# AGV_Schematic.net
KiCad netlist of a schematic drawn in Altium Designer
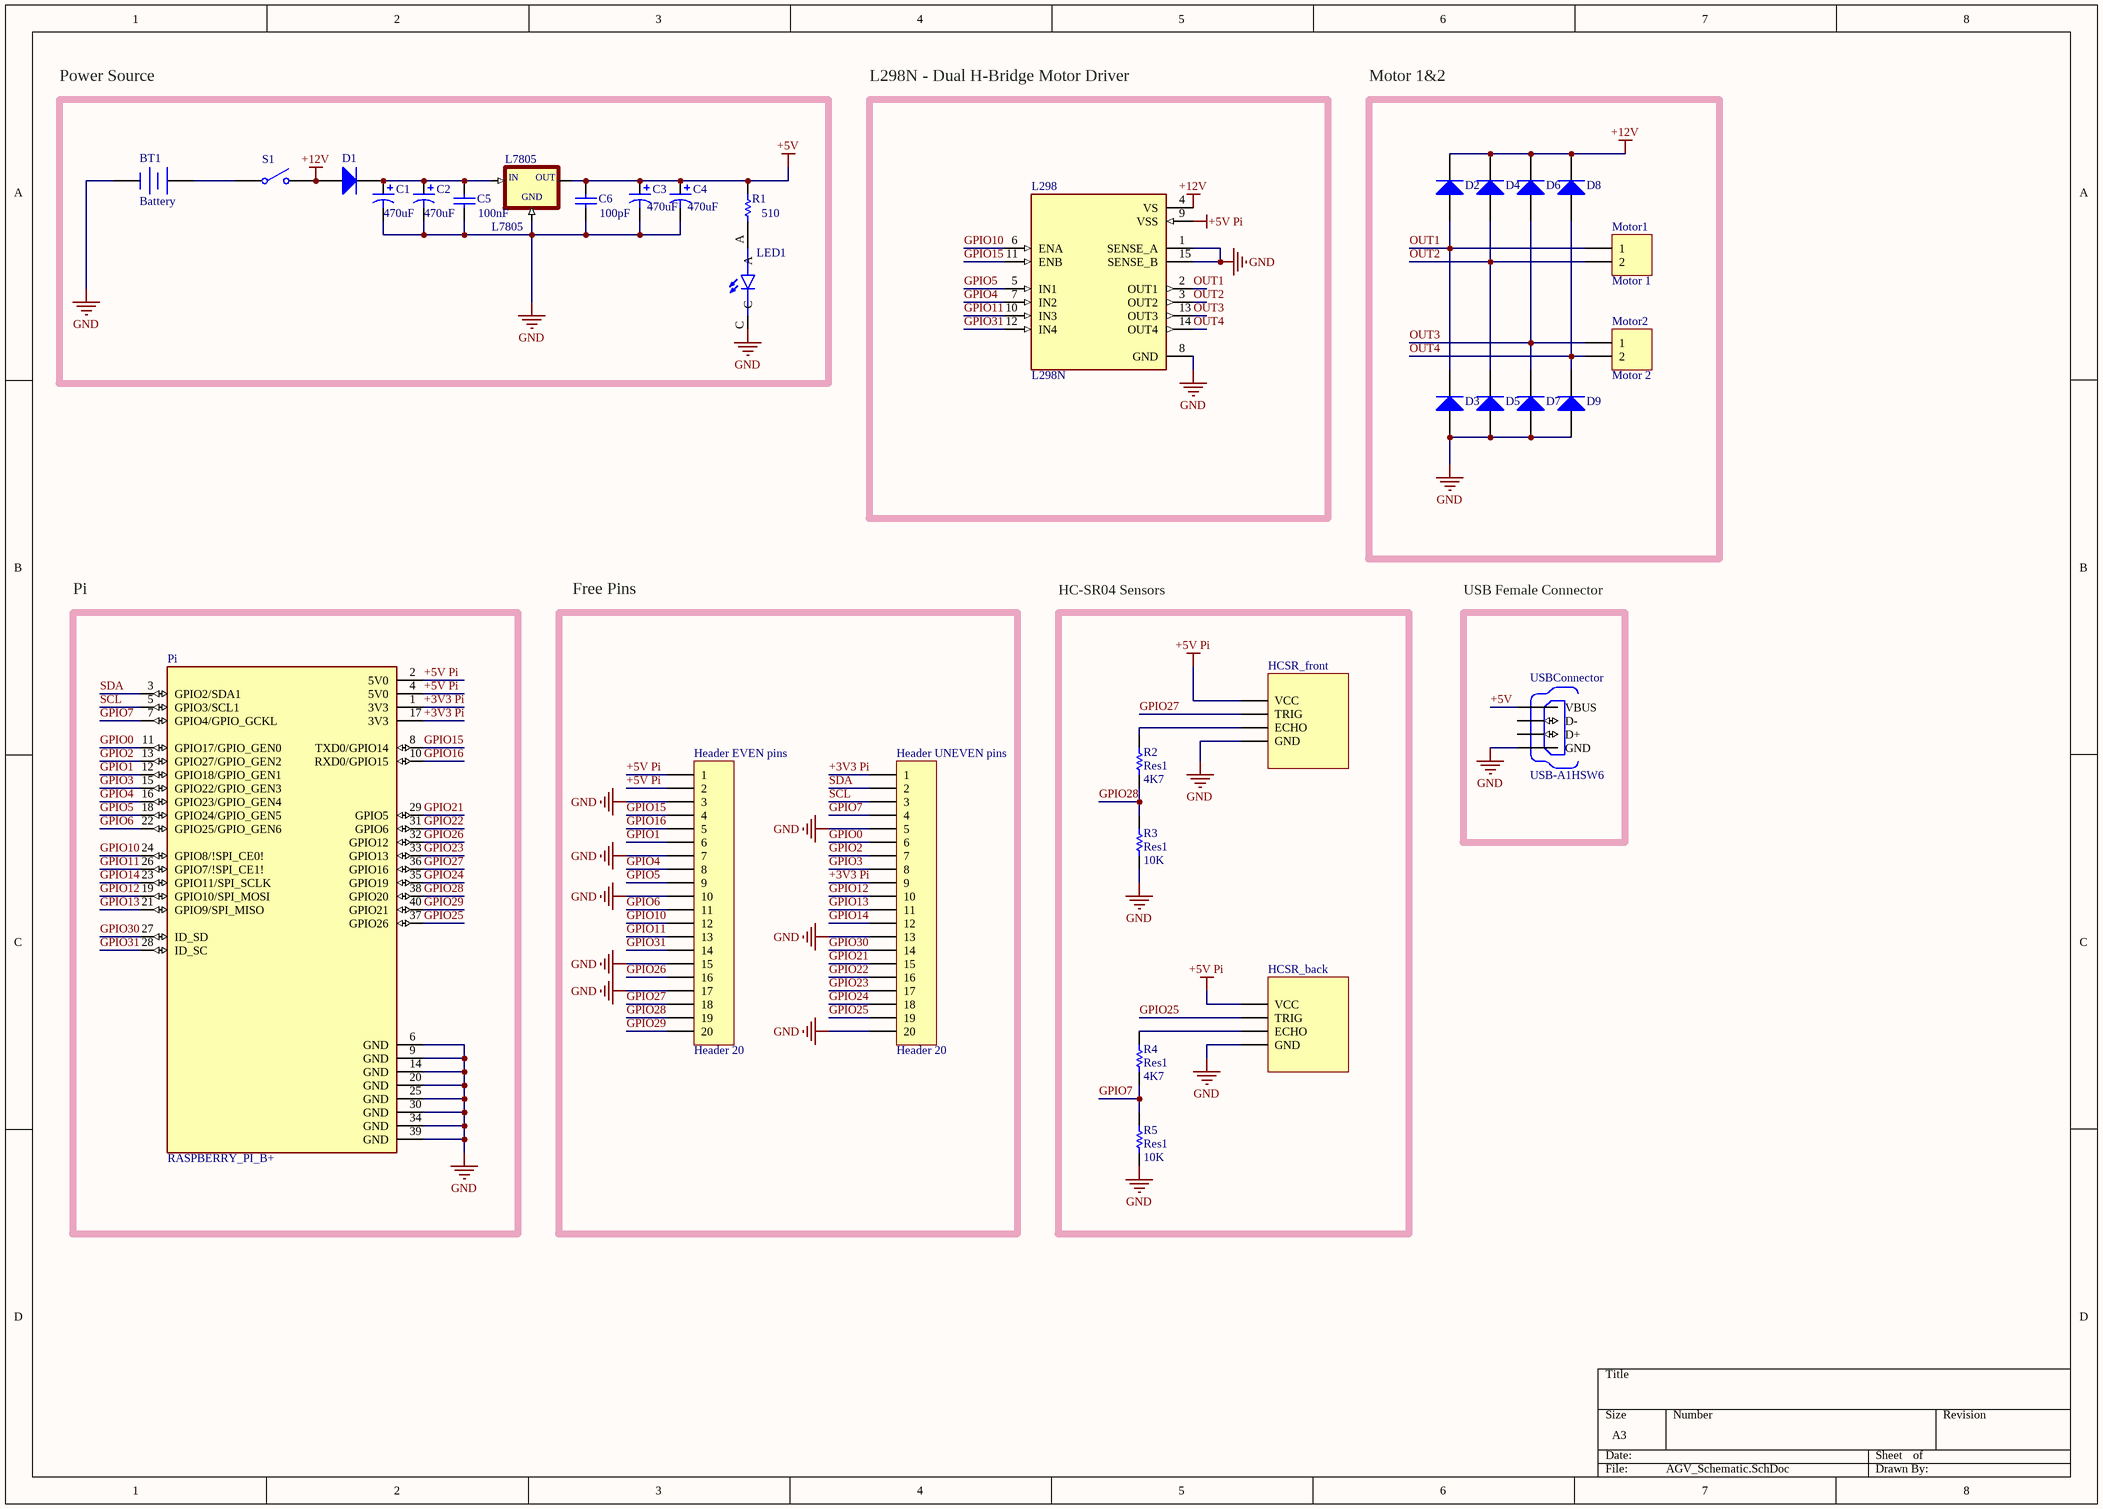
[diagram p0: AGV_Schematic.SchDoc]

(export (version "E")
  (design (tool "Eeschema 10.0.6"))
  (components
    (comp (ref "BT1")
      (value "Battery")
      (footprint "PCBComponent_1")
      (description "Multicell Battery")
      (fields (field (name "PUBLISHER") "Altium Limited"))
      (libsource (lib "Miscellaneous Devices") (part "Battery"))
    )
    (comp (ref "C1")
      (value "470uF")
      (footprint "elektrolitski_kond:Elektrolitski kondenzator")
      (description "Polarized Capacitor (Radial)")
      (fields (field (name "Comment") "Cap Pol1") (field (name "PUBLISHER") "Altium Limited"))
      (libsource (lib "elektrolitski_kond") (part "Elektrolitski kondenzator"))
    )
    (comp (ref "C2")
      (value "470uF")
      (footprint "elektrolitski_kond:Elektrolitski kondenzator")
      (description "Polarized Capacitor (Radial)")
      (fields (field (name "Comment") "Cap Pol1") (field (name "PUBLISHER") "Altium Limited"))
      (libsource (lib "elektrolitski_kond") (part "Elektrolitski kondenzator"))
    )
    (comp (ref "C3")
      (value "470uF")
      (footprint "elektrolitski_kond:Elektrolitski kondenzator")
      (description "Polarized Capacitor (Radial)")
      (fields (field (name "Comment") "Cap Pol1") (field (name "PUBLISHER") "Altium Limited"))
      (libsource (lib "elektrolitski_kond") (part "Elektrolitski kondenzator"))
    )
    (comp (ref "C4")
      (value "470uF")
      (footprint "elektrolitski_kond:Elektrolitski kondenzator")
      (description "Polarized Capacitor (Radial)")
      (fields (field (name "Comment") "Cap Pol1") (field (name "PUBLISHER") "Altium Limited"))
      (libsource (lib "elektrolitski_kond") (part "Elektrolitski kondenzator"))
    )
    (comp (ref "C5")
      (value "100nF")
      (footprint "CAP:CAP140")
      (description "Capacitor")
      (fields (field (name "Comment") "Cap") (field (name "PUBLISHER") "Altium Limited"))
      (libsource (lib "Miscellaneous Devices") (part "Cap"))
    )
    (comp (ref "C6")
      (value "100pF")
      (footprint "CAP:CAP140")
      (description "Capacitor")
      (fields (field (name "Comment") "Cap") (field (name "PUBLISHER") "Altium Limited"))
      (libsource (lib "Miscellaneous Devices") (part "Cap"))
    )
    (comp (ref "D1")
      (value "Diode 1N4007")
      (footprint "DO-41")
      (description "1 Amp General Purpose Rectifier")
      (fields (field (name "PUBLISHER") "Altium Limited"))
      (libsource (lib "Miscellaneous Devices") (part "Diode 1N4007"))
    )
    (comp (ref "D2")
      (value "Diode 1N5402")
      (footprint "DO-41")
      (description "3 Amp General Purpose Rectifier")
      (fields (field (name "PUBLISHER") "Altium Limited"))
      (libsource (lib "Miscellaneous Devices") (part "Diode 1N5402"))
    )
    (comp (ref "D3")
      (value "Diode 1N5402")
      (footprint "DO-41")
      (description "3 Amp General Purpose Rectifier")
      (fields (field (name "PUBLISHER") "Altium Limited"))
      (libsource (lib "Miscellaneous Devices") (part "Diode 1N5402"))
    )
    (comp (ref "D4")
      (value "Diode 1N5402")
      (footprint "DO-41")
      (description "3 Amp General Purpose Rectifier")
      (fields (field (name "PUBLISHER") "Altium Limited"))
      (libsource (lib "Miscellaneous Devices") (part "Diode 1N5402"))
    )
    (comp (ref "D5")
      (value "Diode 1N5402")
      (footprint "DO-41")
      (description "3 Amp General Purpose Rectifier")
      (fields (field (name "PUBLISHER") "Altium Limited"))
      (libsource (lib "Miscellaneous Devices") (part "Diode 1N5402"))
    )
    (comp (ref "D6")
      (value "Diode 1N5402")
      (footprint "DO-41")
      (description "3 Amp General Purpose Rectifier")
      (fields (field (name "PUBLISHER") "Altium Limited"))
      (libsource (lib "Miscellaneous Devices") (part "Diode 1N5402"))
    )
    (comp (ref "D7")
      (value "Diode 1N5402")
      (footprint "DO-41")
      (description "3 Amp General Purpose Rectifier")
      (fields (field (name "PUBLISHER") "Altium Limited"))
      (libsource (lib "Miscellaneous Devices") (part "Diode 1N5402"))
    )
    (comp (ref "D8")
      (value "Diode 1N5402")
      (footprint "DO-41")
      (description "3 Amp General Purpose Rectifier")
      (fields (field (name "PUBLISHER") "Altium Limited"))
      (libsource (lib "Miscellaneous Devices") (part "Diode 1N5402"))
    )
    (comp (ref "D9")
      (value "Diode 1N5402")
      (footprint "DO-41")
      (description "3 Amp General Purpose Rectifier")
      (fields (field (name "PUBLISHER") "Altium Limited"))
      (libsource (lib "Miscellaneous Devices") (part "Diode 1N5402"))
    )
    (comp (ref "HCSR_back") (value "~") (footprint "HDR1X4") (libsource (lib "Komponente") (part "HC-SR04")))
    (comp (ref "HCSR_front") (value "~") (footprint "HDR1X4") (libsource (lib "Komponente") (part "HC-SR04")))
    (comp (ref "Header EVEN pins")
      (value "Header 20")
      (footprint "HDR1X20")
      (description "Header, 20-Pin")
      (fields (field (name "PUBLISHER") "Altium Limited"))
      (libsource (lib "Miscellaneous Connectors") (part "Header 20"))
    )
    (comp (ref "Header UNEVEN pins")
      (value "Header 20")
      (footprint "HDR1X20")
      (description "Header, 20-Pin")
      (fields (field (name "PUBLISHER") "Altium Limited"))
      (libsource (lib "Miscellaneous Connectors") (part "Header 20"))
    )
    (comp (ref "L298")
      (value "L298N")
      (footprint "TO127P2020X500X2100-15")
      (description "Dual Full Bridge Motor Driver 15-Pin(15+Tab) MULTIWATT V Tube")
      (libsource (lib "L298N") (part "L298N"))
    )
    (comp (ref "L7805")
      (value "L7805")
      (footprint "78XXS")
      (description "Linear Voltage Regulator IC 1 Output 1.5A D2PAK")
      (fields (field (name "MF") "STMicroelectronics"))
      (libsource (lib "L7805") (part "L7805"))
    )
    (comp (ref "LED1")
      (value "*")
      (footprint "LED_WP7113LGD")
      (fields (field (name "MP") "WP7113LGD") (field (name "MF") "Kingbright"))
      (libsource (lib "WP7113LGD") (part "WP7113LGD"))
    )
    (comp (ref "Motor1")
      (value "Motor 1")
      (footprint "PCBComponent_1")
      (description "Header, 2-Pin")
      (fields (field (name "PUBLISHER") "Altium Limited"))
      (libsource (lib "Miscellaneous Connectors") (part "Header 2"))
    )
    (comp (ref "Motor2")
      (value "Motor 2")
      (footprint "PCBComponent_1")
      (description "Header, 2-Pin")
      (fields (field (name "PUBLISHER") "Altium Limited"))
      (libsource (lib "Miscellaneous Connectors") (part "Header 2"))
    )
    (comp (ref "Pi")
      (value "RASPBERRY_PI_B+")
      (footprint "PiMirror")
      (description "BCM2835 Raspberry Pi Model B+ - ARM11, VideoCore MPU Embedded Evaluation Board")
      (fields (field (name "MF") "Raspberry Pi") (field (name "MP") "RASPBERRY PI B+"))
      (libsource (lib "RASPBERRY_PI_B_") (part "RASPBERRY_PI_B+"))
    )
    (comp (ref "R1")
      (value "510")
      (footprint "AXIAL-0.3")
      (description "Resistor")
      (fields (field (name "Comment") "Res1") (field (name "PUBLISHER") "Altium Limited"))
      (libsource (lib "Miscellaneous Devices") (part "Res1"))
    )
    (comp (ref "R2")
      (value "Res1")
      (footprint "AXIAL-0.3")
      (description "Resistor")
      (fields (field (name "ALTIUM_VALUE") "4K7") (field (name "PUBLISHER") "Altium Limited"))
      (libsource (lib "Miscellaneous Devices") (part "Res1"))
    )
    (comp (ref "R3")
      (value "Res1")
      (footprint "AXIAL-0.3")
      (description "Resistor")
      (fields (field (name "ALTIUM_VALUE") "10K") (field (name "PUBLISHER") "Altium Limited"))
      (libsource (lib "Miscellaneous Devices") (part "Res1"))
    )
    (comp (ref "R4")
      (value "Res1")
      (footprint "AXIAL-0.3")
      (description "Resistor")
      (fields (field (name "ALTIUM_VALUE") "4K7") (field (name "PUBLISHER") "Altium Limited"))
      (libsource (lib "Miscellaneous Devices") (part "Res1"))
    )
    (comp (ref "R5")
      (value "Res1")
      (footprint "AXIAL-0.3")
      (description "Resistor")
      (fields (field (name "ALTIUM_VALUE") "10K") (field (name "PUBLISHER") "Altium Limited"))
      (libsource (lib "Miscellaneous Devices") (part "Res1"))
    )
    (comp (ref "S1")
      (value "SW-SPST")
      (footprint "Prekidac:Prekidac")
      (description "Single-Pole, Single-Throw Switch")
      (fields (field (name "PUBLISHER") "Altium Limited"))
      (libsource (lib "Miscellaneous Devices") (part "SW-SPST"))
    )
    (comp (ref "USBConnector")
      (value "USB-A1HSW6")
      (footprint "OST_USB-A1HSW6")
      (description "USB-A (USB TYPE-A) - Receptacle Connector 4 Position Through Hole, Right Angle")
      (fields (field (name "MF") "On Shore"))
      (libsource (lib "USB-A1HSW6") (part "USB-A1HSW6"))
    )
  )
  (nets
    (net (code "1") (name "+5V") (class "Default")
      (node (ref "C3") (pin "1") (pinfunction "1_1") (pintype "passive"))
      (node (ref "C4") (pin "1") (pinfunction "1_1") (pintype "passive"))
      (node (ref "C6") (pin "2") (pinfunction "2_2") (pintype "passive"))
      (node (ref "L7805") (pin "OUT") (pinfunction "OUT_OUT") (pintype "passive"))
      (node (ref "R1") (pin "2") (pinfunction "2_2") (pintype "passive"))
      (node (ref "USBConnector") (pin "1") (pinfunction "VBUS_1") (pintype "power_in"))
    )
    (net (code "2") (name "+5V Pi") (class "Default")
      (node (ref "HCSR_back") (pin "1") (pinfunction "VCC_1") (pintype "passive"))
      (node (ref "HCSR_front") (pin "1") (pinfunction "VCC_1") (pintype "passive"))
      (node (ref "Header EVEN pins") (pin "1") (pinfunction "1_1") (pintype "passive"))
      (node (ref "Header EVEN pins") (pin "2") (pinfunction "2_2") (pintype "passive"))
      (node (ref "L298") (pin "9") (pinfunction "VSS_9") (pintype "input"))
      (node (ref "Pi") (pin "2") (pinfunction "5V0_2") (pintype "power_in"))
      (node (ref "Pi") (pin "4") (pinfunction "5V0_4") (pintype "power_in"))
    )
    (net (code "3") (name "+12V") (class "Default")
      (node (ref "D1") (pin "1") (pinfunction "A_1") (pintype "passive"))
      (node (ref "D2") (pin "2") (pinfunction "K_2") (pintype "passive"))
      (node (ref "D4") (pin "2") (pinfunction "K_2") (pintype "passive"))
      (node (ref "D6") (pin "2") (pinfunction "K_2") (pintype "passive"))
      (node (ref "D8") (pin "2") (pinfunction "K_2") (pintype "passive"))
      (node (ref "L298") (pin "4") (pinfunction "VS_4") (pintype "power_in"))
      (node (ref "S1") (pin "2") (pinfunction "NO_2") (pintype "passive"))
    )
    (net (code "4") (name "/+3V3 Pi") (class "Default")
      (node (ref "Header UNEVEN pins") (pin "1") (pinfunction "1_1") (pintype "passive"))
      (node (ref "Header UNEVEN pins") (pin "9") (pinfunction "9_9") (pintype "passive"))
      (node (ref "Pi") (pin "1") (pinfunction "3V3_1") (pintype "power_in"))
      (node (ref "Pi") (pin "17") (pinfunction "3V3_17") (pintype "power_in"))
    )
    (net (code "5") (name "/GPIO0") (class "Default")
      (node (ref "Header UNEVEN pins") (pin "6") (pinfunction "6_6") (pintype "passive"))
      (node (ref "Pi") (pin "11") (pinfunction "GPIO17/GPIO_GEN0_11") (pintype "bidirectional"))
    )
    (net (code "6") (name "/GPIO1") (class "Default")
      (node (ref "Header EVEN pins") (pin "6") (pinfunction "6_6") (pintype "passive"))
      (node (ref "Pi") (pin "12") (pinfunction "GPIO18/GPIO_GEN1_12") (pintype "bidirectional"))
    )
    (net (code "7") (name "/GPIO2") (class "Default")
      (node (ref "Header UNEVEN pins") (pin "7") (pinfunction "7_7") (pintype "passive"))
      (node (ref "Pi") (pin "13") (pinfunction "GPIO27/GPIO_GEN2_13") (pintype "bidirectional"))
    )
    (net (code "8") (name "/GPIO3") (class "Default")
      (node (ref "Header UNEVEN pins") (pin "8") (pinfunction "8_8") (pintype "passive"))
      (node (ref "Pi") (pin "15") (pinfunction "GPIO22/GPIO_GEN3_15") (pintype "bidirectional"))
    )
    (net (code "9") (name "/GPIO4") (class "Default")
      (node (ref "Header EVEN pins") (pin "8") (pinfunction "8_8") (pintype "passive"))
      (node (ref "L298") (pin "7") (pinfunction "IN2_7") (pintype "input"))
      (node (ref "Pi") (pin "16") (pinfunction "GPIO23/GPIO_GEN4_16") (pintype "bidirectional"))
    )
    (net (code "10") (name "/GPIO5") (class "Default")
      (node (ref "Header EVEN pins") (pin "9") (pinfunction "9_9") (pintype "passive"))
      (node (ref "L298") (pin "5") (pinfunction "IN1_5") (pintype "input"))
      (node (ref "Pi") (pin "18") (pinfunction "GPIO24/GPIO_GEN5_18") (pintype "bidirectional"))
    )
    (net (code "11") (name "/GPIO6") (class "Default")
      (node (ref "Header EVEN pins") (pin "11") (pinfunction "11_11") (pintype "passive"))
      (node (ref "Pi") (pin "22") (pinfunction "GPIO25/GPIO_GEN6_22") (pintype "bidirectional"))
    )
    (net (code "12") (name "/GPIO7") (class "Default")
      (node (ref "Header UNEVEN pins") (pin "4") (pinfunction "4_4") (pintype "passive"))
      (node (ref "Pi") (pin "7") (pinfunction "GPIO4/GPIO_GCKL_7") (pintype "bidirectional"))
      (node (ref "R4") (pin "1") (pinfunction "1_1") (pintype "passive"))
      (node (ref "R5") (pin "2") (pinfunction "2_2") (pintype "passive"))
    )
    (net (code "13") (name "/GPIO10") (class "Default")
      (node (ref "Header EVEN pins") (pin "12") (pinfunction "12_12") (pintype "passive"))
      (node (ref "L298") (pin "6") (pinfunction "ENA_6") (pintype "input"))
      (node (ref "Pi") (pin "24") (pinfunction "GPIO8/!SPI_CE0!_24") (pintype "bidirectional"))
    )
    (net (code "14") (name "/GPIO11") (class "Default")
      (node (ref "Header EVEN pins") (pin "13") (pinfunction "13_13") (pintype "passive"))
      (node (ref "L298") (pin "10") (pinfunction "IN3_10") (pintype "input"))
      (node (ref "Pi") (pin "26") (pinfunction "GPIO7/!SPI_CE1!_26") (pintype "bidirectional"))
    )
    (net (code "15") (name "/GPIO12") (class "Default")
      (node (ref "Header UNEVEN pins") (pin "10") (pinfunction "10_10") (pintype "passive"))
      (node (ref "Pi") (pin "19") (pinfunction "GPIO10/SPI_MOSI_19") (pintype "bidirectional"))
    )
    (net (code "16") (name "/GPIO13") (class "Default")
      (node (ref "Header UNEVEN pins") (pin "11") (pinfunction "11_11") (pintype "passive"))
      (node (ref "Pi") (pin "21") (pinfunction "GPIO9/SPI_MISO_21") (pintype "bidirectional"))
    )
    (net (code "17") (name "/GPIO14") (class "Default")
      (node (ref "Header UNEVEN pins") (pin "12") (pinfunction "12_12") (pintype "passive"))
      (node (ref "Pi") (pin "23") (pinfunction "GPIO11/SPI_SCLK_23") (pintype "bidirectional"))
    )
    (net (code "18") (name "/GPIO15") (class "Default")
      (node (ref "Header EVEN pins") (pin "4") (pinfunction "4_4") (pintype "passive"))
      (node (ref "L298") (pin "11") (pinfunction "ENB_11") (pintype "input"))
      (node (ref "Pi") (pin "8") (pinfunction "TXD0/GPIO14_8") (pintype "bidirectional"))
    )
    (net (code "19") (name "/GPIO16") (class "Default")
      (node (ref "Header EVEN pins") (pin "5") (pinfunction "5_5") (pintype "passive"))
      (node (ref "Pi") (pin "10") (pinfunction "RXD0/GPIO15_10") (pintype "bidirectional"))
    )
    (net (code "20") (name "/GPIO21") (class "Default")
      (node (ref "Header UNEVEN pins") (pin "15") (pinfunction "15_15") (pintype "passive"))
      (node (ref "Pi") (pin "29") (pinfunction "GPIO5_29") (pintype "bidirectional"))
    )
    (net (code "21") (name "/GPIO22") (class "Default")
      (node (ref "Header UNEVEN pins") (pin "16") (pinfunction "16_16") (pintype "passive"))
      (node (ref "Pi") (pin "31") (pinfunction "GPIO6_31") (pintype "bidirectional"))
    )
    (net (code "22") (name "/GPIO23") (class "Default")
      (node (ref "Header UNEVEN pins") (pin "17") (pinfunction "17_17") (pintype "passive"))
      (node (ref "Pi") (pin "33") (pinfunction "GPIO13_33") (pintype "bidirectional"))
    )
    (net (code "23") (name "/GPIO24") (class "Default")
      (node (ref "Header UNEVEN pins") (pin "18") (pinfunction "18_18") (pintype "passive"))
      (node (ref "Pi") (pin "35") (pinfunction "GPIO19_35") (pintype "bidirectional"))
    )
    (net (code "24") (name "/GPIO25") (class "Default")
      (node (ref "HCSR_back") (pin "2") (pinfunction "TRIG_2") (pintype "passive"))
      (node (ref "Header UNEVEN pins") (pin "19") (pinfunction "19_19") (pintype "passive"))
      (node (ref "Pi") (pin "37") (pinfunction "GPIO26_37") (pintype "bidirectional"))
    )
    (net (code "25") (name "/GPIO26") (class "Default")
      (node (ref "Header EVEN pins") (pin "16") (pinfunction "16_16") (pintype "passive"))
      (node (ref "Pi") (pin "32") (pinfunction "GPIO12_32") (pintype "bidirectional"))
    )
    (net (code "26") (name "/GPIO27") (class "Default")
      (node (ref "HCSR_front") (pin "2") (pinfunction "TRIG_2") (pintype "passive"))
      (node (ref "Header EVEN pins") (pin "18") (pinfunction "18_18") (pintype "passive"))
      (node (ref "Pi") (pin "36") (pinfunction "GPIO16_36") (pintype "bidirectional"))
    )
    (net (code "27") (name "/GPIO28") (class "Default")
      (node (ref "Header EVEN pins") (pin "19") (pinfunction "19_19") (pintype "passive"))
      (node (ref "Pi") (pin "38") (pinfunction "GPIO20_38") (pintype "bidirectional"))
      (node (ref "R2") (pin "1") (pinfunction "1_1") (pintype "passive"))
      (node (ref "R3") (pin "2") (pinfunction "2_2") (pintype "passive"))
    )
    (net (code "28") (name "/GPIO29") (class "Default")
      (node (ref "Header EVEN pins") (pin "20") (pinfunction "20_20") (pintype "passive"))
      (node (ref "Pi") (pin "40") (pinfunction "GPIO21_40") (pintype "bidirectional"))
    )
    (net (code "29") (name "/GPIO30") (class "Default")
      (node (ref "Header UNEVEN pins") (pin "14") (pinfunction "14_14") (pintype "passive"))
      (node (ref "Pi") (pin "27") (pinfunction "ID_SD_27") (pintype "bidirectional"))
    )
    (net (code "30") (name "/GPIO31") (class "Default")
      (node (ref "Header EVEN pins") (pin "14") (pinfunction "14_14") (pintype "passive"))
      (node (ref "L298") (pin "12") (pinfunction "IN4_12") (pintype "input"))
      (node (ref "Pi") (pin "28") (pinfunction "ID_SC_28") (pintype "bidirectional"))
    )
    (net (code "31") (name "/OUT1") (class "Default")
      (node (ref "D2") (pin "1") (pinfunction "A_1") (pintype "passive"))
      (node (ref "D3") (pin "2") (pinfunction "K_2") (pintype "passive"))
      (node (ref "L298") (pin "2") (pinfunction "OUT1_2") (pintype "output"))
      (node (ref "Motor1") (pin "1") (pinfunction "1_1") (pintype "passive"))
    )
    (net (code "32") (name "/OUT2") (class "Default")
      (node (ref "D4") (pin "1") (pinfunction "A_1") (pintype "passive"))
      (node (ref "D5") (pin "2") (pinfunction "K_2") (pintype "passive"))
      (node (ref "L298") (pin "3") (pinfunction "OUT2_3") (pintype "output"))
      (node (ref "Motor1") (pin "2") (pinfunction "2_2") (pintype "passive"))
    )
    (net (code "33") (name "/OUT3") (class "Default")
      (node (ref "D6") (pin "1") (pinfunction "A_1") (pintype "passive"))
      (node (ref "D7") (pin "2") (pinfunction "K_2") (pintype "passive"))
      (node (ref "L298") (pin "13") (pinfunction "OUT3_13") (pintype "output"))
      (node (ref "Motor2") (pin "1") (pinfunction "1_1") (pintype "passive"))
    )
    (net (code "34") (name "/OUT4") (class "Default")
      (node (ref "D8") (pin "1") (pinfunction "A_1") (pintype "passive"))
      (node (ref "D9") (pin "2") (pinfunction "K_2") (pintype "passive"))
      (node (ref "L298") (pin "14") (pinfunction "OUT4_14") (pintype "output"))
      (node (ref "Motor2") (pin "2") (pinfunction "2_2") (pintype "passive"))
    )
    (net (code "35") (name "/SCL") (class "Default")
      (node (ref "Header UNEVEN pins") (pin "3") (pinfunction "3_3") (pintype "passive"))
      (node (ref "Pi") (pin "5") (pinfunction "GPIO3/SCL1_5") (pintype "bidirectional"))
    )
    (net (code "36") (name "/SDA") (class "Default")
      (node (ref "Header UNEVEN pins") (pin "2") (pinfunction "2_2") (pintype "passive"))
      (node (ref "Pi") (pin "3") (pinfunction "GPIO2/SDA1_3") (pintype "bidirectional"))
    )
    (net (code "37") (name "GND") (class "Default")
      (node (ref "BT1") (pin "2") (pinfunction "-_2") (pintype "passive"))
      (node (ref "C1") (pin "2") (pinfunction "2_2") (pintype "passive"))
      (node (ref "C2") (pin "2") (pinfunction "2_2") (pintype "passive"))
      (node (ref "C3") (pin "2") (pinfunction "2_2") (pintype "passive"))
      (node (ref "C4") (pin "2") (pinfunction "2_2") (pintype "passive"))
      (node (ref "C5") (pin "1") (pinfunction "1_1") (pintype "passive"))
      (node (ref "C6") (pin "1") (pinfunction "1_1") (pintype "passive"))
      (node (ref "D3") (pin "1") (pinfunction "A_1") (pintype "passive"))
      (node (ref "D5") (pin "1") (pinfunction "A_1") (pintype "passive"))
      (node (ref "D7") (pin "1") (pinfunction "A_1") (pintype "passive"))
      (node (ref "D9") (pin "1") (pinfunction "A_1") (pintype "passive"))
      (node (ref "HCSR_back") (pin "4") (pinfunction "GND_4") (pintype "passive"))
      (node (ref "HCSR_front") (pin "4") (pinfunction "GND_4") (pintype "passive"))
      (node (ref "Header EVEN pins") (pin "10") (pinfunction "10_10") (pintype "passive"))
      (node (ref "Header EVEN pins") (pin "15") (pinfunction "15_15") (pintype "passive"))
      (node (ref "Header EVEN pins") (pin "17") (pinfunction "17_17") (pintype "passive"))
      (node (ref "Header EVEN pins") (pin "3") (pinfunction "3_3") (pintype "passive"))
      (node (ref "Header EVEN pins") (pin "7") (pinfunction "7_7") (pintype "passive"))
      (node (ref "Header UNEVEN pins") (pin "13") (pinfunction "13_13") (pintype "passive"))
      (node (ref "Header UNEVEN pins") (pin "20") (pinfunction "20_20") (pintype "passive"))
      (node (ref "Header UNEVEN pins") (pin "5") (pinfunction "5_5") (pintype "passive"))
      (node (ref "L298") (pin "1") (pinfunction "SENSE_A_1") (pintype "passive"))
      (node (ref "L298") (pin "15") (pinfunction "SENSE_B_15") (pintype "passive"))
      (node (ref "L298") (pin "8") (pinfunction "GND_8") (pintype "power_in"))
      (node (ref "L7805") (pin "GND") (pinfunction "GND_GND") (pintype "input"))
      (node (ref "LED1") (pin "C") (pinfunction "C_C") (pintype "passive"))
      (node (ref "Pi") (pin "14") (pinfunction "GND_14") (pintype "power_in"))
      (node (ref "Pi") (pin "20") (pinfunction "GND_20") (pintype "power_in"))
      (node (ref "Pi") (pin "25") (pinfunction "GND_25") (pintype "power_in"))
      (node (ref "Pi") (pin "30") (pinfunction "GND_30") (pintype "power_in"))
      (node (ref "Pi") (pin "34") (pinfunction "GND_34") (pintype "power_in"))
      (node (ref "Pi") (pin "39") (pinfunction "GND_39") (pintype "power_in"))
      (node (ref "Pi") (pin "6") (pinfunction "GND_6") (pintype "power_in"))
      (node (ref "Pi") (pin "9") (pinfunction "GND_9") (pintype "power_in"))
      (node (ref "R3") (pin "1") (pinfunction "1_1") (pintype "passive"))
      (node (ref "R5") (pin "1") (pinfunction "1_1") (pintype "passive"))
      (node (ref "USBConnector") (pin "4") (pinfunction "GND_4") (pintype "power_in"))
    )
    (net (code "38") (name "Net-(BT1-+)") (class "Default")
      (node (ref "BT1") (pin "1") (pinfunction "+_1") (pintype "passive"))
      (node (ref "S1") (pin "1") (pinfunction "COMMON_1") (pintype "passive"))
    )
    (net (code "39") (name "Net-(D1-K)") (class "Default")
      (node (ref "C1") (pin "1") (pinfunction "1_1") (pintype "passive"))
      (node (ref "C2") (pin "1") (pinfunction "1_1") (pintype "passive"))
      (node (ref "C5") (pin "2") (pinfunction "2_2") (pintype "passive"))
      (node (ref "D1") (pin "2") (pinfunction "K_2") (pintype "passive"))
      (node (ref "L7805") (pin "IN") (pinfunction "IN_IN") (pintype "input"))
    )
    (net (code "40") (name "Net-(HCSR_back-ECHO)") (class "Default")
      (node (ref "HCSR_back") (pin "3") (pinfunction "ECHO_3") (pintype "passive"))
      (node (ref "R4") (pin "2") (pinfunction "2_2") (pintype "passive"))
    )
    (net (code "41") (name "Net-(HCSR_front-ECHO)") (class "Default")
      (node (ref "HCSR_front") (pin "3") (pinfunction "ECHO_3") (pintype "passive"))
      (node (ref "R2") (pin "2") (pinfunction "2_2") (pintype "passive"))
    )
    (net (code "42") (name "Net-(LED1-PadA)") (class "Default")
      (node (ref "LED1") (pin "A") (pinfunction "A_A") (pintype "passive"))
      (node (ref "R1") (pin "1") (pinfunction "1_1") (pintype "passive"))
    )
    (net (code "43") (name "unconnected-(USBConnector-D+-Pad3)") (class "Default")
      (node (ref "USBConnector") (pin "3") (pinfunction "D+_3") (pintype "bidirectional"))
    )
    (net (code "44") (name "unconnected-(USBConnector-D--Pad2)") (class "Default")
      (node (ref "USBConnector") (pin "2") (pinfunction "D-_2") (pintype "bidirectional"))
    )
  )
)
